# fotel_color.net
KiCad netlist of a schematic drawn in Altium Designer
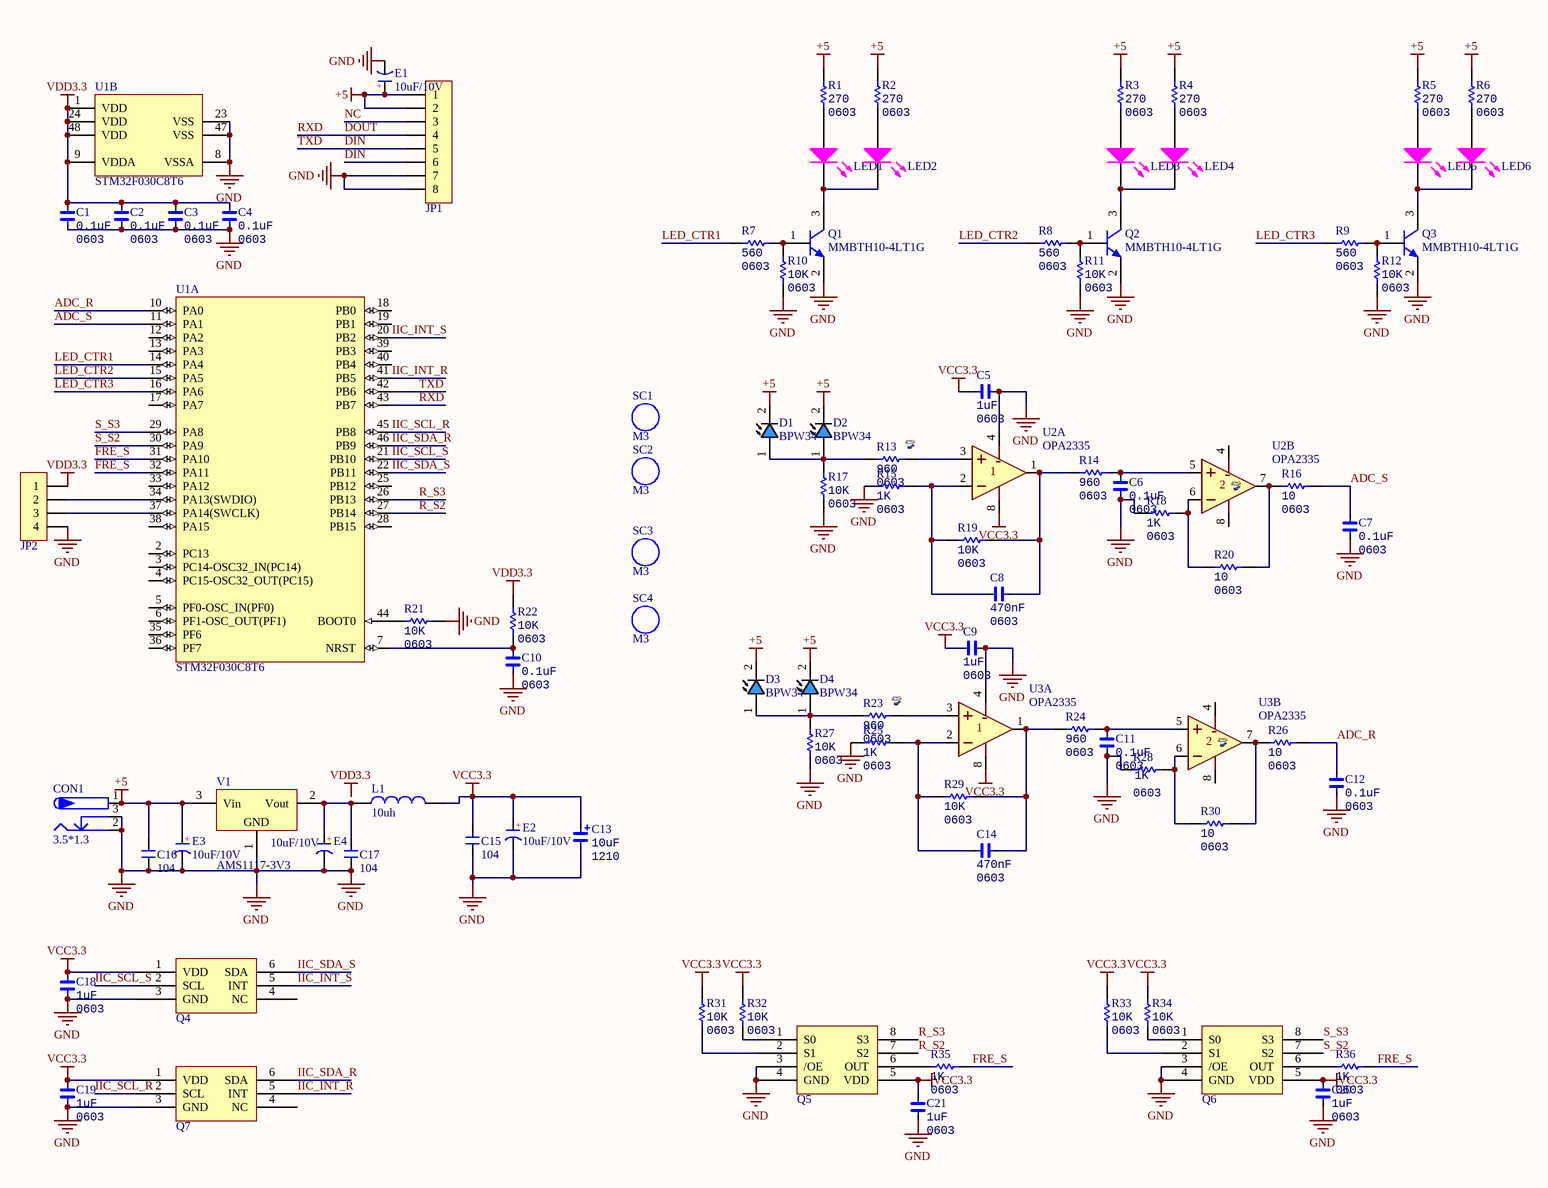
[diagram p0: fotel_color.SchDoc]

(export (version "E")
  (design (tool "Eeschema 10.0.6"))
  (components
    (comp (ref "C1")
      (value "0.1uF")
      (footprint "CAP_0603")
      (description "Capacitor")
      (fields (field (name "TYPE") "0603") (field (name "Comment") "C0402"))
      (libsource (lib "Capacitors") (part "Cap_0603"))
    )
    (comp (ref "C2")
      (value "0.1uF")
      (footprint "CAP_0603")
      (description "Capacitor")
      (fields (field (name "TYPE") "0603") (field (name "Comment") "C0402"))
      (libsource (lib "Capacitors") (part "Cap_0603"))
    )
    (comp (ref "C3")
      (value "0.1uF")
      (footprint "CAP_0603")
      (description "Capacitor")
      (fields (field (name "TYPE") "0603") (field (name "Comment") "C0402"))
      (libsource (lib "Capacitors") (part "Cap_0603"))
    )
    (comp (ref "C4")
      (value "0.1uF")
      (footprint "CAP_0603")
      (description "Capacitor")
      (fields (field (name "TYPE") "0603") (field (name "Comment") "C0402"))
      (libsource (lib "Capacitors") (part "Cap_0603"))
    )
    (comp (ref "C5")
      (value "1uF")
      (footprint "CAP_0603")
      (description "Capacitor")
      (fields (field (name "TYPE") "0603") (field (name "Comment") "C0402"))
      (libsource (lib "") (part "Cap_0603_1"))
    )
    (comp (ref "C6")
      (value "0.1uF")
      (footprint "CAP_0603")
      (description "Capacitor")
      (fields (field (name "TYPE") "0603") (field (name "Comment") "C0402"))
      (libsource (lib "Capacitors") (part "Cap_0603"))
    )
    (comp (ref "C7")
      (value "0.1uF")
      (footprint "CAP_0603")
      (description "Capacitor")
      (fields (field (name "TYPE") "0603") (field (name "Comment") "C0402"))
      (libsource (lib "Capacitors") (part "Cap_0603"))
    )
    (comp (ref "C8")
      (value "470nF")
      (footprint "CAP_0603")
      (description "Capacitor")
      (fields (field (name "TYPE") "0603") (field (name "Comment") "C0402"))
      (libsource (lib "") (part "Cap_0603_2"))
    )
    (comp (ref "C9")
      (value "1uF")
      (footprint "CAP_0603")
      (description "Capacitor")
      (fields (field (name "TYPE") "0603") (field (name "Comment") "C0402"))
      (libsource (lib "") (part "Cap_0603_1"))
    )
    (comp (ref "C10")
      (value "0.1uF")
      (footprint "CAP_0603")
      (description "Capacitor")
      (fields (field (name "TYPE") "0603") (field (name "Comment") "C0402"))
      (libsource (lib "") (part "Cap_0603_3"))
    )
    (comp (ref "C11")
      (value "0.1uF")
      (footprint "CAP_0603")
      (description "Capacitor")
      (fields (field (name "TYPE") "0603") (field (name "Comment") "C0402"))
      (libsource (lib "Capacitors") (part "Cap_0603"))
    )
    (comp (ref "C12")
      (value "0.1uF")
      (footprint "CAP_0603")
      (description "Capacitor")
      (fields (field (name "TYPE") "0603") (field (name "Comment") "C0402"))
      (libsource (lib "Capacitors") (part "Cap_0603"))
    )
    (comp (ref "C13")
      (value "10uF")
      (footprint "CAP_TAN_B1210")
      (description "Capacitor Tantalum")
      (fields (field (name "TYPE") "1210") (field (name "Comment") "C1210"))
      (libsource (lib "Capacitors") (part "Cap_Tan_1210"))
    )
    (comp (ref "C14")
      (value "470nF")
      (footprint "CAP_0603")
      (description "Capacitor")
      (fields (field (name "TYPE") "0603") (field (name "Comment") "C0402"))
      (libsource (lib "") (part "Cap_0603_2"))
    )
    (comp (ref "C15")
      (value "104")
      (footprint "C 0603")
      (description "无极性贴片电容")
      (fields (field (name "版权归属") "黎明电子style"))
      (libsource (lib "电阻-电容-电感") (part "C"))
    )
    (comp (ref "C16")
      (value "104")
      (footprint "C 0603")
      (description "无极性贴片电容")
      (fields (field (name "版权归属") "黎明电子style"))
      (libsource (lib "电阻-电容-电感") (part "C"))
    )
    (comp (ref "C17")
      (value "104")
      (footprint "C 0603")
      (description "无极性贴片电容")
      (fields (field (name "版权归属") "黎明电子style"))
      (libsource (lib "电阻-电容-电感") (part "C"))
    )
    (comp (ref "C18")
      (value "1uF")
      (footprint "CAP_0603")
      (description "Capacitor")
      (fields (field (name "TYPE") "0603") (field (name "Comment") "C0402"))
      (libsource (lib "Capacitors") (part "Cap_0603"))
    )
    (comp (ref "C19")
      (value "1uF")
      (footprint "CAP_0603")
      (description "Capacitor")
      (fields (field (name "TYPE") "0603") (field (name "Comment") "C0402"))
      (libsource (lib "Capacitors") (part "Cap_0603"))
    )
    (comp (ref "C20")
      (value "1uF")
      (footprint "CAP_0603")
      (description "Capacitor")
      (fields (field (name "TYPE") "0603") (field (name "Comment") "C0402"))
      (libsource (lib "Capacitors") (part "Cap_0603"))
    )
    (comp (ref "C21")
      (value "1uF")
      (footprint "CAP_0603")
      (description "Capacitor")
      (fields (field (name "TYPE") "0603") (field (name "Comment") "C0402"))
      (libsource (lib "Capacitors") (part "Cap_0603"))
    )
    (comp (ref "CON1")
      (value "3.5*1.3")
      (footprint "DC-005")
      (description "低压电源接口")
      (fields (field (name "版权归属") "黎明电子style"))
      (libsource (lib "接口类") (part "P-DC"))
    )
    (comp (ref "D1")
      (value "BPW34")
      (footprint "TEMD5510")
      (description "Photodiode, 2nA, 32Vr, 20ns, 60deg, 850nm")
      (fields (field (name "MANF") "OSRAM, VISHAY") (field (name "MANF_P#") "BPW34BS, BPW34S"))
      (libsource (lib "IC") (part "PHDIODE_BPW34S"))
    )
    (comp (ref "D2")
      (value "BPW34")
      (footprint "CLS15")
      (description "Photodiode, 2nA, 32Vr, 20ns, 60deg, 850nm")
      (fields (field (name "MANF") "OSRAM, VISHAY") (field (name "MANF_P#") "BPW34BS, BPW34S"))
      (libsource (lib "IC") (part "PHDIODE_BPW34S"))
    )
    (comp (ref "D3")
      (value "BPW34")
      (footprint "TEMD5510")
      (description "Photodiode, 2nA, 32Vr, 20ns, 60deg, 850nm")
      (fields (field (name "MANF") "OSRAM, VISHAY") (field (name "MANF_P#") "BPW34BS, BPW34S"))
      (libsource (lib "IC") (part "PHDIODE_BPW34S"))
    )
    (comp (ref "D4")
      (value "BPW34")
      (footprint "CLS15")
      (description "Photodiode, 2nA, 32Vr, 20ns, 60deg, 850nm")
      (fields (field (name "MANF") "OSRAM, VISHAY") (field (name "MANF_P#") "BPW34BS, BPW34S"))
      (libsource (lib "IC") (part "PHDIODE_BPW34S"))
    )
    (comp (ref "E1")
      (value "10uF/10V")
      (footprint "CM D(6.3*5.4)")
      (description "贴片电解电容")
      (fields (field (name "版权归属") "黎明电子style"))
      (libsource (lib "电阻-电容-电感") (part "C-CM"))
    )
    (comp (ref "E2")
      (value "10uF/10V")
      (footprint "CM D(6.3*5.4)")
      (description "贴片电解电容")
      (fields (field (name "版权归属") "黎明电子style"))
      (libsource (lib "电阻-电容-电感") (part "C-CM"))
    )
    (comp (ref "E3")
      (value "10uF/10V")
      (footprint "CM D(6.3*5.4)")
      (description "贴片电解电容")
      (fields (field (name "版权归属") "黎明电子style"))
      (libsource (lib "电阻-电容-电感") (part "C-CM"))
    )
    (comp (ref "E4")
      (value "10uF/10V")
      (footprint "CM D(6.3*5.4)")
      (description "贴片电解电容")
      (fields (field (name "版权归属") "黎明电子style"))
      (libsource (lib "电阻-电容-电感") (part "C-CM"))
    )
    (comp (ref "JP1")
      (value "HDR-1X8")
      (footprint "PH2.0 S-W-8P")
      (description "8P接插件")
      (fields (field (name "版权归属") "黎明电子style"))
      (libsource (lib "接插件") (part "Header 8"))
    )
    (comp (ref "JP2")
      (value "HDR-1X4")
      (footprint "XH2.54-4P")
      (description "4P接插件")
      (fields (field (name "版权归属") "黎明电子style"))
      (libsource (lib "接插件") (part "Header 4"))
    )
    (comp (ref "L1")
      (value "10uh")
      (footprint "L 0603")
      (description "小功率贴片电感")
      (fields (field (name "版权归属") "黎明电子style"))
      (libsource (lib "电阻-电容-电感") (part "L"))
    )
    (comp (ref "LED1")
      (value "LED-3-R")
      (footprint "LED-R3-H5-SINGLE-R")
      (description "Typical INFRARED GaAs LED")
      (fields (field (name "PUBLISHER") "Altium Limited"))
      (libsource (lib "(NEW)DRC_MD Library") (part "LED-3-R"))
    )
    (comp (ref "LED2")
      (value "LED-3-R")
      (footprint "LED-R3-H5-SINGLE-R")
      (description "Typical INFRARED GaAs LED")
      (fields (field (name "PUBLISHER") "Altium Limited"))
      (libsource (lib "(NEW)DRC_MD Library") (part "LED-3-R"))
    )
    (comp (ref "LED3")
      (value "LED-3-R")
      (footprint "LED-R3-H5-SINGLE-R")
      (description "Typical INFRARED GaAs LED")
      (fields (field (name "PUBLISHER") "Altium Limited"))
      (libsource (lib "(NEW)DRC_MD Library") (part "LED-3-R"))
    )
    (comp (ref "LED4")
      (value "LED-3-R")
      (footprint "LED-R3-H5-SINGLE-R")
      (description "Typical INFRARED GaAs LED")
      (fields (field (name "PUBLISHER") "Altium Limited"))
      (libsource (lib "(NEW)DRC_MD Library") (part "LED-3-R"))
    )
    (comp (ref "LED5")
      (value "LED-3-R")
      (footprint "LED-R3-H5-SINGLE-R")
      (description "Typical INFRARED GaAs LED")
      (fields (field (name "PUBLISHER") "Altium Limited"))
      (libsource (lib "(NEW)DRC_MD Library") (part "LED-3-R"))
    )
    (comp (ref "LED6")
      (value "LED-3-R")
      (footprint "LED-R3-H5-SINGLE-R")
      (description "Typical INFRARED GaAs LED")
      (fields (field (name "PUBLISHER") "Altium Limited"))
      (libsource (lib "(NEW)DRC_MD Library") (part "LED-3-R"))
    )
    (comp (ref "Q1")
      (value "MMBTH10-4LT1G")
      (footprint "ONSC-SOT-23-3-318-08_V")
      (description "VHF / UHF Transistor, NPN Silicon, 3-Pin SOT-23, Pb-Free, Tape and Reel")
      (fields (field (name "MANUFACTURER") "On Semiconductor"))
      (libsource (lib "Transistor") (part "MMBTH10-4LT1G"))
    )
    (comp (ref "Q2")
      (value "MMBTH10-4LT1G")
      (footprint "ONSC-SOT-23-3-318-08_V")
      (description "VHF / UHF Transistor, NPN Silicon, 3-Pin SOT-23, Pb-Free, Tape and Reel")
      (fields (field (name "MANUFACTURER") "On Semiconductor"))
      (libsource (lib "Transistor") (part "MMBTH10-4LT1G"))
    )
    (comp (ref "Q3")
      (value "MMBTH10-4LT1G")
      (footprint "ONSC-SOT-23-3-318-08_V")
      (description "VHF / UHF Transistor, NPN Silicon, 3-Pin SOT-23, Pb-Free, Tape and Reel")
      (fields (field (name "MANUFACTURER") "On Semiconductor"))
      (libsource (lib "Transistor") (part "MMBTH10-4LT1G"))
    )
    (comp (ref "Q4")
      (value "~")
      (footprint "TCS34725")
      (description "Phototransistor,IIC")
      (libsource (lib "IC") (part "TCS34725"))
    )
    (comp (ref "Q5")
      (value "~")
      (footprint "SOP-8")
      (description "Phototransistor,digit")
      (libsource (lib "IC") (part "TCS3200"))
    )
    (comp (ref "Q6")
      (value "~")
      (footprint "SOP-8")
      (description "Phototransistor,digit")
      (libsource (lib "IC") (part "TCS3200"))
    )
    (comp (ref "Q7")
      (value "~")
      (footprint "TCS34725")
      (description "Phototransistor,IIC")
      (libsource (lib "IC") (part "TCS34725"))
    )
    (comp (ref "R1")
      (value "270")
      (footprint "RES_0603")
      (description "Resistor")
      (fields (field (name "TYPE") "0603"))
      (libsource (lib "Resistors") (part "Res_0603"))
    )
    (comp (ref "R2")
      (value "270")
      (footprint "RES_0603")
      (description "Resistor")
      (fields (field (name "TYPE") "0603"))
      (libsource (lib "Resistors") (part "Res_0603"))
    )
    (comp (ref "R3")
      (value "270")
      (footprint "RES_0603")
      (description "Resistor")
      (fields (field (name "TYPE") "0603"))
      (libsource (lib "Resistors") (part "Res_0603"))
    )
    (comp (ref "R4")
      (value "270")
      (footprint "RES_0603")
      (description "Resistor")
      (fields (field (name "TYPE") "0603"))
      (libsource (lib "Resistors") (part "Res_0603"))
    )
    (comp (ref "R5")
      (value "270")
      (footprint "RES_0603")
      (description "Resistor")
      (fields (field (name "TYPE") "0603"))
      (libsource (lib "Resistors") (part "Res_0603"))
    )
    (comp (ref "R6")
      (value "270")
      (footprint "RES_0603")
      (description "Resistor")
      (fields (field (name "TYPE") "0603"))
      (libsource (lib "Resistors") (part "Res_0603"))
    )
    (comp (ref "R7")
      (value "560")
      (footprint "RES_0603")
      (description "Resistor")
      (fields (field (name "TYPE") "0603"))
      (libsource (lib "Resistors") (part "Res_0603"))
    )
    (comp (ref "R8")
      (value "560")
      (footprint "RES_0603")
      (description "Resistor")
      (fields (field (name "TYPE") "0603"))
      (libsource (lib "Resistors") (part "Res_0603"))
    )
    (comp (ref "R9")
      (value "560")
      (footprint "RES_0603")
      (description "Resistor")
      (fields (field (name "TYPE") "0603"))
      (libsource (lib "Resistors") (part "Res_0603"))
    )
    (comp (ref "R10")
      (value "10K")
      (footprint "RES_0603")
      (description "Resistor")
      (fields (field (name "TYPE") "0603"))
      (libsource (lib "Resistors") (part "Res_0603"))
    )
    (comp (ref "R11")
      (value "10K")
      (footprint "RES_0603")
      (description "Resistor")
      (fields (field (name "TYPE") "0603"))
      (libsource (lib "Resistors") (part "Res_0603"))
    )
    (comp (ref "R12")
      (value "10K")
      (footprint "RES_0603")
      (description "Resistor")
      (fields (field (name "TYPE") "0603"))
      (libsource (lib "Resistors") (part "Res_0603"))
    )
    (comp (ref "R13")
      (value "960")
      (footprint "RES_0603")
      (description "Resistor")
      (fields (field (name "TYPE") "0603"))
      (libsource (lib "Resistors") (part "Res_0603"))
    )
    (comp (ref "R14")
      (value "960")
      (footprint "RES_0603")
      (description "Resistor")
      (fields (field (name "TYPE") "0603"))
      (libsource (lib "Resistors") (part "Res_0603"))
    )
    (comp (ref "R15")
      (value "1K")
      (footprint "RES_0603")
      (description "Resistor")
      (fields (field (name "TYPE") "0603"))
      (libsource (lib "Resistors") (part "Res_0603"))
    )
    (comp (ref "R16")
      (value "10")
      (footprint "RES_0603")
      (description "Resistor")
      (fields (field (name "TYPE") "0603"))
      (libsource (lib "Resistors") (part "Res_0603"))
    )
    (comp (ref "R17")
      (value "10K")
      (footprint "RES_0603")
      (description "Resistor")
      (fields (field (name "TYPE") "0603"))
      (libsource (lib "Resistors") (part "Res_0603"))
    )
    (comp (ref "R18")
      (value "1K")
      (footprint "RES_0603")
      (description "Resistor")
      (fields (field (name "TYPE") "0603"))
      (libsource (lib "Resistors") (part "Res_0603"))
    )
    (comp (ref "R19")
      (value "10K")
      (footprint "RES_0603")
      (description "Resistor")
      (fields (field (name "TYPE") "0603"))
      (libsource (lib "Resistors") (part "Res_0603"))
    )
    (comp (ref "R20")
      (value "10")
      (footprint "RES_0603")
      (description "Resistor")
      (fields (field (name "TYPE") "0603"))
      (libsource (lib "Resistors") (part "Res_0603"))
    )
    (comp (ref "R21")
      (value "10K")
      (footprint "RES_0603")
      (description "Resistor")
      (fields (field (name "TYPE") "0603"))
      (libsource (lib "Resistors") (part "Res_0603"))
    )
    (comp (ref "R22")
      (value "10K")
      (footprint "RES_0603")
      (description "Resistor")
      (fields (field (name "TYPE") "0603"))
      (libsource (lib "Resistors") (part "Res_0603"))
    )
    (comp (ref "R23")
      (value "960")
      (footprint "RES_0603")
      (description "Resistor")
      (fields (field (name "TYPE") "0603"))
      (libsource (lib "Resistors") (part "Res_0603"))
    )
    (comp (ref "R24")
      (value "960")
      (footprint "RES_0603")
      (description "Resistor")
      (fields (field (name "TYPE") "0603"))
      (libsource (lib "Resistors") (part "Res_0603"))
    )
    (comp (ref "R25")
      (value "1K")
      (footprint "RES_0603")
      (description "Resistor")
      (fields (field (name "TYPE") "0603"))
      (libsource (lib "Resistors") (part "Res_0603"))
    )
    (comp (ref "R26")
      (value "10")
      (footprint "RES_0603")
      (description "Resistor")
      (fields (field (name "TYPE") "0603"))
      (libsource (lib "Resistors") (part "Res_0603"))
    )
    (comp (ref "R27")
      (value "10K")
      (footprint "RES_0603")
      (description "Resistor")
      (fields (field (name "TYPE") "0603"))
      (libsource (lib "Resistors") (part "Res_0603"))
    )
    (comp (ref "R28")
      (value "1K")
      (footprint "RES_0603")
      (description "Resistor")
      (fields (field (name "TYPE") "0603"))
      (libsource (lib "Resistors") (part "Res_0603"))
    )
    (comp (ref "R29")
      (value "10K")
      (footprint "RES_0603")
      (description "Resistor")
      (fields (field (name "TYPE") "0603"))
      (libsource (lib "Resistors") (part "Res_0603"))
    )
    (comp (ref "R30")
      (value "10")
      (footprint "RES_0603")
      (description "Resistor")
      (fields (field (name "TYPE") "0603"))
      (libsource (lib "Resistors") (part "Res_0603"))
    )
    (comp (ref "R31")
      (value "10K")
      (footprint "RES_0603")
      (description "Resistor")
      (fields (field (name "TYPE") "0603"))
      (libsource (lib "Resistors") (part "Res_0603"))
    )
    (comp (ref "R32")
      (value "10K")
      (footprint "RES_0603")
      (description "Resistor")
      (fields (field (name "TYPE") "0603"))
      (libsource (lib "Resistors") (part "Res_0603"))
    )
    (comp (ref "R33")
      (value "10K")
      (footprint "RES_0603")
      (description "Resistor")
      (fields (field (name "TYPE") "0603"))
      (libsource (lib "Resistors") (part "Res_0603"))
    )
    (comp (ref "R34")
      (value "10K")
      (footprint "RES_0603")
      (description "Resistor")
      (fields (field (name "TYPE") "0603"))
      (libsource (lib "Resistors") (part "Res_0603"))
    )
    (comp (ref "R35")
      (value "1K")
      (footprint "RES_0603")
      (description "Resistor")
      (fields (field (name "TYPE") "0603"))
      (libsource (lib "Resistors") (part "Res_0603"))
    )
    (comp (ref "R36")
      (value "1K")
      (footprint "RES_0603")
      (description "Resistor")
      (fields (field (name "TYPE") "0603"))
      (libsource (lib "Resistors") (part "Res_0603"))
    )
    (comp (ref "SC1")
      (value "M3")
      (footprint "M3 125X200")
      (description "铜柱孔")
      (fields (field (name "版权归属") "黎明电子style"))
      (libsource (lib "未分类器件") (part "M3"))
    )
    (comp (ref "SC2")
      (value "M3")
      (footprint "M3 125X200")
      (description "铜柱孔")
      (fields (field (name "版权归属") "黎明电子style"))
      (libsource (lib "未分类器件") (part "M3"))
    )
    (comp (ref "SC3")
      (value "M3")
      (footprint "M3 125X200")
      (description "铜柱孔")
      (fields (field (name "版权归属") "黎明电子style"))
      (libsource (lib "未分类器件") (part "M3"))
    )
    (comp (ref "SC4")
      (value "M3")
      (footprint "M3 125X200")
      (description "铜柱孔")
      (fields (field (name "版权归属") "黎明电子style"))
      (libsource (lib "未分类器件") (part "M3"))
    )
    (comp (ref "U1")
      (value "STM32F030C8T6")
      (footprint "LQFP48 7X7_M")
      (libsource (lib "IC") (part "STM32F030C8T6"))
    )
    (comp (ref "U2")
      (value "OPA2335")
      (footprint "SOG65_8_3")
      (description "AMP, Low Offset, Zero Drift, Single-Supply")
      (fields (field (name "MANF") "Texas Instruments") (field (name "MANF_P#") "OPA2335AIDGK"))
      (libsource (lib "IC") (part "OPA2335_SSOP8"))
    )
    (comp (ref "U3")
      (value "OPA2335")
      (footprint "SOG65_8_3")
      (description "AMP, Low Offset, Zero Drift, Single-Supply")
      (fields (field (name "MANF") "Texas Instruments") (field (name "MANF_P#") "OPA2335AIDGK"))
      (libsource (lib "IC") (part "OPA2335_SSOP8"))
    )
    (comp (ref "V1")
      (value "AMS1117-3V3")
      (footprint "SOT223_L")
      (description "三端稳压芯片")
      (fields (field (name "版权归属") "黎明电子style"))
      (libsource (lib "IC芯片") (part "AMS1117"))
    )
  )
  (nets
    (net (code "1") (name "+5") (class "Default")
      (node (ref "C16") (pin "2") (pinfunction "2_2") (pintype "passive"))
      (node (ref "CON1") (pin "1") (pintype "power_in"))
      (node (ref "D1") (pin "2") (pinfunction "CATHODE_2") (pintype "passive"))
      (node (ref "D2") (pin "2") (pinfunction "CATHODE_2") (pintype "passive"))
      (node (ref "D3") (pin "2") (pinfunction "CATHODE_2") (pintype "passive"))
      (node (ref "D4") (pin "2") (pinfunction "CATHODE_2") (pintype "passive"))
      (node (ref "E1") (pin "1") (pinfunction "A_1") (pintype "passive"))
      (node (ref "E3") (pin "1") (pinfunction "A_1") (pintype "passive"))
      (node (ref "JP1") (pin "1") (pinfunction "1_1") (pintype "passive"))
      (node (ref "JP1") (pin "2") (pinfunction "2_2") (pintype "passive"))
      (node (ref "R1") (pin "2") (pinfunction "2_2") (pintype "passive"))
      (node (ref "R2") (pin "2") (pinfunction "2_2") (pintype "passive"))
      (node (ref "R3") (pin "2") (pinfunction "2_2") (pintype "passive"))
      (node (ref "R4") (pin "2") (pinfunction "2_2") (pintype "passive"))
      (node (ref "R5") (pin "2") (pinfunction "2_2") (pintype "passive"))
      (node (ref "R6") (pin "2") (pinfunction "2_2") (pintype "passive"))
      (node (ref "V1") (pin "3") (pinfunction "Vin_3") (pintype "passive"))
    )
    (net (code "2") (name "/ADC_R") (class "Default")
      (node (ref "C12") (pin "1") (pinfunction "1_1") (pintype "passive"))
      (node (ref "R26") (pin "2") (pinfunction "2_2") (pintype "passive"))
      (node (ref "U1") (pin "10") (pinfunction "PA0_10") (pintype "bidirectional"))
    )
    (net (code "3") (name "/ADC_S") (class "Default")
      (node (ref "C7") (pin "1") (pinfunction "1_1") (pintype "passive"))
      (node (ref "R16") (pin "2") (pinfunction "2_2") (pintype "passive"))
      (node (ref "U1") (pin "11") (pinfunction "PA1_11") (pintype "bidirectional"))
    )
    (net (code "4") (name "/DIN") (class "Default")
      (node (ref "JP1") (pin "5") (pinfunction "5_5") (pintype "passive"))
      (node (ref "JP1") (pin "6") (pinfunction "6_6") (pintype "passive"))
      (node (ref "U1") (pin "42") (pinfunction "PB6_42") (pintype "bidirectional"))
    )
    (net (code "5") (name "/DOUT") (class "Default")
      (node (ref "JP1") (pin "4") (pinfunction "4_4") (pintype "passive"))
      (node (ref "U1") (pin "43") (pinfunction "PB7_43") (pintype "bidirectional"))
    )
    (net (code "6") (name "/FRE_S") (class "Default")
      (node (ref "R35") (pin "1") (pinfunction "1_1") (pintype "passive"))
      (node (ref "R36") (pin "1") (pinfunction "1_1") (pintype "passive"))
      (node (ref "U1") (pin "31") (pinfunction "PA10_31") (pintype "bidirectional"))
      (node (ref "U1") (pin "32") (pinfunction "PA11_32") (pintype "bidirectional"))
    )
    (net (code "7") (name "/IIC_INT_R") (class "Default")
      (node (ref "Q7") (pin "5") (pinfunction "INT_5") (pintype "passive"))
      (node (ref "U1") (pin "41") (pinfunction "PB5_41") (pintype "bidirectional"))
    )
    (net (code "8") (name "/IIC_INT_S") (class "Default")
      (node (ref "Q4") (pin "5") (pinfunction "INT_5") (pintype "passive"))
      (node (ref "U1") (pin "20") (pinfunction "PB2_20") (pintype "bidirectional"))
    )
    (net (code "9") (name "/IIC_SCL_R") (class "Default")
      (node (ref "Q7") (pin "2") (pinfunction "SCL_2") (pintype "passive"))
      (node (ref "U1") (pin "45") (pinfunction "PB8_45") (pintype "bidirectional"))
    )
    (net (code "10") (name "/IIC_SCL_S") (class "Default")
      (node (ref "Q4") (pin "2") (pinfunction "SCL_2") (pintype "passive"))
      (node (ref "U1") (pin "21") (pinfunction "PB10_21") (pintype "bidirectional"))
    )
    (net (code "11") (name "/IIC_SDA_R") (class "Default")
      (node (ref "Q7") (pin "6") (pinfunction "SDA_6") (pintype "passive"))
      (node (ref "U1") (pin "46") (pinfunction "PB9_46") (pintype "bidirectional"))
    )
    (net (code "12") (name "/IIC_SDA_S") (class "Default")
      (node (ref "Q4") (pin "6") (pinfunction "SDA_6") (pintype "passive"))
      (node (ref "U1") (pin "22") (pinfunction "PB11_22") (pintype "bidirectional"))
    )
    (net (code "13") (name "/LED_CTR1") (class "Default")
      (node (ref "R7") (pin "1") (pinfunction "1_1") (pintype "passive"))
      (node (ref "U1") (pin "14") (pinfunction "PA4_14") (pintype "bidirectional"))
    )
    (net (code "14") (name "/LED_CTR2") (class "Default")
      (node (ref "R8") (pin "1") (pinfunction "1_1") (pintype "passive"))
      (node (ref "U1") (pin "15") (pinfunction "PA5_15") (pintype "bidirectional"))
    )
    (net (code "15") (name "/LED_CTR3") (class "Default")
      (node (ref "R9") (pin "1") (pinfunction "1_1") (pintype "passive"))
      (node (ref "U1") (pin "16") (pinfunction "PA6_16") (pintype "bidirectional"))
    )
    (net (code "16") (name "/NC") (class "Default")
      (node (ref "JP1") (pin "3") (pinfunction "3_3") (pintype "passive"))
    )
    (net (code "17") (name "/R_S2") (class "Default")
      (node (ref "Q5") (pin "7") (pinfunction "S2_7") (pintype "passive"))
      (node (ref "U1") (pin "27") (pinfunction "PB14_27") (pintype "bidirectional"))
    )
    (net (code "18") (name "/R_S3") (class "Default")
      (node (ref "Q5") (pin "8") (pinfunction "S3_8") (pintype "passive"))
      (node (ref "U1") (pin "26") (pinfunction "PB13_26") (pintype "bidirectional"))
    )
    (net (code "19") (name "/S_S2") (class "Default")
      (node (ref "Q6") (pin "7") (pinfunction "S2_7") (pintype "passive"))
      (node (ref "U1") (pin "30") (pinfunction "PA9_30") (pintype "bidirectional"))
    )
    (net (code "20") (name "/S_S3") (class "Default")
      (node (ref "Q6") (pin "8") (pinfunction "S3_8") (pintype "passive"))
      (node (ref "U1") (pin "29") (pinfunction "PA8_29") (pintype "bidirectional"))
    )
    (net (code "21") (name "GND") (class "Default")
      (node (ref "C1") (pin "2") (pinfunction "2_2") (pintype "passive"))
      (node (ref "C10") (pin "1") (pinfunction "1_1") (pintype "passive"))
      (node (ref "C11") (pin "2") (pinfunction "2_2") (pintype "passive"))
      (node (ref "C12") (pin "2") (pinfunction "2_2") (pintype "passive"))
      (node (ref "C13") (pin "2") (pinfunction "2_2") (pintype "passive"))
      (node (ref "C15") (pin "1") (pinfunction "1_1") (pintype "passive"))
      (node (ref "C16") (pin "1") (pinfunction "1_1") (pintype "passive"))
      (node (ref "C17") (pin "1") (pinfunction "1_1") (pintype "passive"))
      (node (ref "C18") (pin "2") (pinfunction "2_2") (pintype "passive"))
      (node (ref "C19") (pin "2") (pinfunction "2_2") (pintype "passive"))
      (node (ref "C2") (pin "2") (pinfunction "2_2") (pintype "passive"))
      (node (ref "C20") (pin "2") (pinfunction "2_2") (pintype "passive"))
      (node (ref "C21") (pin "2") (pinfunction "2_2") (pintype "passive"))
      (node (ref "C3") (pin "2") (pinfunction "2_2") (pintype "passive"))
      (node (ref "C4") (pin "2") (pinfunction "2_2") (pintype "passive"))
      (node (ref "C5") (pin "2") (pinfunction "2_2") (pintype "passive"))
      (node (ref "C6") (pin "2") (pinfunction "2_2") (pintype "passive"))
      (node (ref "C7") (pin "2") (pinfunction "2_2") (pintype "passive"))
      (node (ref "C9") (pin "2") (pinfunction "2_2") (pintype "passive"))
      (node (ref "CON1") (pin "2") (pintype "power_in"))
      (node (ref "CON1") (pin "3") (pintype "power_in"))
      (node (ref "E1") (pin "2") (pinfunction "K_2") (pintype "passive"))
      (node (ref "E2") (pin "2") (pinfunction "K_2") (pintype "passive"))
      (node (ref "E3") (pin "2") (pinfunction "K_2") (pintype "passive"))
      (node (ref "E4") (pin "2") (pinfunction "K_2") (pintype "passive"))
      (node (ref "JP1") (pin "7") (pinfunction "7_7") (pintype "passive"))
      (node (ref "JP1") (pin "8") (pinfunction "8_8") (pintype "passive"))
      (node (ref "JP2") (pin "4") (pinfunction "4_4") (pintype "passive"))
      (node (ref "Q1") (pin "2") (pinfunction "E_2") (pintype "passive"))
      (node (ref "Q2") (pin "2") (pinfunction "E_2") (pintype "passive"))
      (node (ref "Q3") (pin "2") (pinfunction "E_2") (pintype "passive"))
      (node (ref "Q4") (pin "3") (pinfunction "GND_3") (pintype "passive"))
      (node (ref "Q5") (pin "3") (pinfunction "/OE_3") (pintype "passive"))
      (node (ref "Q5") (pin "4") (pinfunction "GND_4") (pintype "passive"))
      (node (ref "Q6") (pin "3") (pinfunction "/OE_3") (pintype "passive"))
      (node (ref "Q6") (pin "4") (pinfunction "GND_4") (pintype "passive"))
      (node (ref "Q7") (pin "3") (pinfunction "GND_3") (pintype "passive"))
      (node (ref "R10") (pin "1") (pinfunction "1_1") (pintype "passive"))
      (node (ref "R11") (pin "1") (pinfunction "1_1") (pintype "passive"))
      (node (ref "R12") (pin "1") (pinfunction "1_1") (pintype "passive"))
      (node (ref "R15") (pin "1") (pinfunction "1_1") (pintype "passive"))
      (node (ref "R17") (pin "1") (pinfunction "1_1") (pintype "passive"))
      (node (ref "R18") (pin "1") (pinfunction "1_1") (pintype "passive"))
      (node (ref "R21") (pin "2") (pinfunction "2_2") (pintype "passive"))
      (node (ref "R25") (pin "1") (pinfunction "1_1") (pintype "passive"))
      (node (ref "R27") (pin "1") (pinfunction "1_1") (pintype "passive"))
      (node (ref "R28") (pin "1") (pinfunction "1_1") (pintype "passive"))
      (node (ref "U1") (pin "23") (pinfunction "VSS_23") (pintype "power_in"))
      (node (ref "U1") (pin "47") (pinfunction "VSS_47") (pintype "power_in"))
      (node (ref "U1") (pin "8") (pinfunction "VSSA_8") (pintype "power_in"))
      (node (ref "U2") (pin "4") (pinfunction "V-_4") (pintype "passive"))
      (node (ref "U3") (pin "4") (pinfunction "V-_4") (pintype "passive"))
      (node (ref "V1") (pin "1") (pinfunction "GND_1") (pintype "passive"))
    )
    (net (code "22") (name "Net-(D1-ANODE)") (class "Default")
      (node (ref "D1") (pin "1") (pinfunction "ANODE_1") (pintype "passive"))
      (node (ref "D2") (pin "1") (pinfunction "ANODE_1") (pintype "passive"))
      (node (ref "R13") (pin "1") (pinfunction "1_1") (pintype "passive"))
      (node (ref "R17") (pin "2") (pinfunction "2_2") (pintype "passive"))
    )
    (net (code "23") (name "Net-(D3-ANODE)") (class "Default")
      (node (ref "D3") (pin "1") (pinfunction "ANODE_1") (pintype "passive"))
      (node (ref "D4") (pin "1") (pinfunction "ANODE_1") (pintype "passive"))
      (node (ref "R23") (pin "1") (pinfunction "1_1") (pintype "passive"))
      (node (ref "R27") (pin "2") (pinfunction "2_2") (pintype "passive"))
    )
    (net (code "24") (name "Net-(E4-A)") (class "Default")
      (node (ref "C17") (pin "2") (pinfunction "2_2") (pintype "passive"))
      (node (ref "E4") (pin "1") (pinfunction "A_1") (pintype "passive"))
      (node (ref "L1") (pin "1") (pinfunction "1_1") (pintype "passive"))
      (node (ref "V1") (pin "2") (pinfunction "Vout_2") (pintype "passive"))
    )
    (net (code "25") (name "Net-(LED1-A)") (class "Default")
      (node (ref "LED1") (pin "1") (pinfunction "A_1") (pintype "passive"))
      (node (ref "R1") (pin "1") (pinfunction "1_1") (pintype "passive"))
    )
    (net (code "26") (name "Net-(LED1-K)") (class "Default")
      (node (ref "LED1") (pin "2") (pinfunction "K_2") (pintype "passive"))
      (node (ref "LED2") (pin "2") (pinfunction "K_2") (pintype "passive"))
      (node (ref "Q1") (pin "3") (pinfunction "C_3") (pintype "passive"))
    )
    (net (code "27") (name "Net-(LED2-A)") (class "Default")
      (node (ref "LED2") (pin "1") (pinfunction "A_1") (pintype "passive"))
      (node (ref "R2") (pin "1") (pinfunction "1_1") (pintype "passive"))
    )
    (net (code "28") (name "Net-(LED3-A)") (class "Default")
      (node (ref "LED3") (pin "1") (pinfunction "A_1") (pintype "passive"))
      (node (ref "R3") (pin "1") (pinfunction "1_1") (pintype "passive"))
    )
    (net (code "29") (name "Net-(LED3-K)") (class "Default")
      (node (ref "LED3") (pin "2") (pinfunction "K_2") (pintype "passive"))
      (node (ref "LED4") (pin "2") (pinfunction "K_2") (pintype "passive"))
      (node (ref "Q2") (pin "3") (pinfunction "C_3") (pintype "passive"))
    )
    (net (code "30") (name "Net-(LED4-A)") (class "Default")
      (node (ref "LED4") (pin "1") (pinfunction "A_1") (pintype "passive"))
      (node (ref "R4") (pin "1") (pinfunction "1_1") (pintype "passive"))
    )
    (net (code "31") (name "Net-(LED5-A)") (class "Default")
      (node (ref "LED5") (pin "1") (pinfunction "A_1") (pintype "passive"))
      (node (ref "R5") (pin "1") (pinfunction "1_1") (pintype "passive"))
    )
    (net (code "32") (name "Net-(LED5-K)") (class "Default")
      (node (ref "LED5") (pin "2") (pinfunction "K_2") (pintype "passive"))
      (node (ref "LED6") (pin "2") (pinfunction "K_2") (pintype "passive"))
      (node (ref "Q3") (pin "3") (pinfunction "C_3") (pintype "passive"))
    )
    (net (code "33") (name "Net-(LED6-A)") (class "Default")
      (node (ref "LED6") (pin "1") (pinfunction "A_1") (pintype "passive"))
      (node (ref "R6") (pin "1") (pinfunction "1_1") (pintype "passive"))
    )
    (net (code "34") (name "Net-(Q1-B)") (class "Default")
      (node (ref "Q1") (pin "1") (pinfunction "B_1") (pintype "passive"))
      (node (ref "R10") (pin "2") (pinfunction "2_2") (pintype "passive"))
      (node (ref "R7") (pin "2") (pinfunction "2_2") (pintype "passive"))
    )
    (net (code "35") (name "Net-(Q2-B)") (class "Default")
      (node (ref "Q2") (pin "1") (pinfunction "B_1") (pintype "passive"))
      (node (ref "R11") (pin "2") (pinfunction "2_2") (pintype "passive"))
      (node (ref "R8") (pin "2") (pinfunction "2_2") (pintype "passive"))
    )
    (net (code "36") (name "Net-(Q3-B)") (class "Default")
      (node (ref "Q3") (pin "1") (pinfunction "B_1") (pintype "passive"))
      (node (ref "R12") (pin "2") (pinfunction "2_2") (pintype "passive"))
      (node (ref "R9") (pin "2") (pinfunction "2_2") (pintype "passive"))
    )
    (net (code "37") (name "Net-(Q5-OUT)") (class "Default")
      (node (ref "Q5") (pin "6") (pinfunction "OUT_6") (pintype "passive"))
      (node (ref "R35") (pin "2") (pinfunction "2_2") (pintype "passive"))
    )
    (net (code "38") (name "Net-(Q5-S0)") (class "Default")
      (node (ref "Q5") (pin "1") (pinfunction "S0_1") (pintype "passive"))
      (node (ref "R32") (pin "1") (pinfunction "1_1") (pintype "passive"))
    )
    (net (code "39") (name "Net-(Q5-S1)") (class "Default")
      (node (ref "Q5") (pin "2") (pinfunction "S1_2") (pintype "passive"))
      (node (ref "R31") (pin "1") (pinfunction "1_1") (pintype "passive"))
    )
    (net (code "40") (name "Net-(Q6-OUT)") (class "Default")
      (node (ref "Q6") (pin "6") (pinfunction "OUT_6") (pintype "passive"))
      (node (ref "R36") (pin "2") (pinfunction "2_2") (pintype "passive"))
    )
    (net (code "41") (name "Net-(Q6-S0)") (class "Default")
      (node (ref "Q6") (pin "1") (pinfunction "S0_1") (pintype "passive"))
      (node (ref "R34") (pin "1") (pinfunction "1_1") (pintype "passive"))
    )
    (net (code "42") (name "Net-(Q6-S1)") (class "Default")
      (node (ref "Q6") (pin "2") (pinfunction "S1_2") (pintype "passive"))
      (node (ref "R33") (pin "1") (pinfunction "1_1") (pintype "passive"))
    )
    (net (code "43") (name "Net-(U1A-BOOT0)") (class "Default")
      (node (ref "R21") (pin "1") (pinfunction "1_1") (pintype "passive"))
      (node (ref "U1") (pin "44") (pinfunction "BOOT0_44") (pintype "input"))
    )
    (net (code "44") (name "Net-(U1A-NRST)") (class "Default")
      (node (ref "C10") (pin "2") (pinfunction "2_2") (pintype "passive"))
      (node (ref "R22") (pin "2") (pinfunction "2_2") (pintype "passive"))
      (node (ref "U1") (pin "7") (pinfunction "NRST_7") (pintype "bidirectional"))
    )
    (net (code "45") (name "Net-(U1A-PA13(SWDIO))") (class "Default")
      (node (ref "JP2") (pin "2") (pinfunction "2_2") (pintype "passive"))
      (node (ref "U1") (pin "34") (pinfunction "PA13(SWDIO)_34") (pintype "bidirectional"))
    )
    (net (code "46") (name "Net-(U1A-PA14(SWCLK))") (class "Default")
      (node (ref "JP2") (pin "3") (pinfunction "3_3") (pintype "passive"))
      (node (ref "U1") (pin "37") (pinfunction "PA14(SWCLK)_37") (pintype "bidirectional"))
    )
    (net (code "47") (name "Net-(U2A-IN+)") (class "Default")
      (node (ref "R13") (pin "2") (pinfunction "2_2") (pintype "passive"))
      (node (ref "U2") (pin "3") (pinfunction "IN+_3") (pintype "passive"))
    )
    (net (code "48") (name "Net-(U2A-IN-)") (class "Default")
      (node (ref "C8") (pin "2") (pinfunction "2_2") (pintype "passive"))
      (node (ref "R15") (pin "2") (pinfunction "2_2") (pintype "passive"))
      (node (ref "R19") (pin "1") (pinfunction "1_1") (pintype "passive"))
      (node (ref "U2") (pin "2") (pinfunction "IN-_2") (pintype "passive"))
    )
    (net (code "49") (name "Net-(U2A-OUT)") (class "Default")
      (node (ref "C8") (pin "1") (pinfunction "1_1") (pintype "passive"))
      (node (ref "R14") (pin "1") (pinfunction "1_1") (pintype "passive"))
      (node (ref "R19") (pin "2") (pinfunction "2_2") (pintype "passive"))
      (node (ref "U2") (pin "1") (pinfunction "OUT_1") (pintype "passive"))
    )
    (net (code "50") (name "Net-(U2B-IN+)") (class "Default")
      (node (ref "C6") (pin "1") (pinfunction "1_1") (pintype "passive"))
      (node (ref "R14") (pin "2") (pinfunction "2_2") (pintype "passive"))
      (node (ref "U2") (pin "5") (pinfunction "IN+_5") (pintype "passive"))
    )
    (net (code "51") (name "Net-(U2B-IN-)") (class "Default")
      (node (ref "R18") (pin "2") (pinfunction "2_2") (pintype "passive"))
      (node (ref "R20") (pin "1") (pinfunction "1_1") (pintype "passive"))
      (node (ref "U2") (pin "6") (pinfunction "IN-_6") (pintype "passive"))
    )
    (net (code "52") (name "Net-(U2B-OUT)") (class "Default")
      (node (ref "R16") (pin "1") (pinfunction "1_1") (pintype "passive"))
      (node (ref "R20") (pin "2") (pinfunction "2_2") (pintype "passive"))
      (node (ref "U2") (pin "7") (pinfunction "OUT_7") (pintype "passive"))
    )
    (net (code "53") (name "Net-(U3A-IN+)") (class "Default")
      (node (ref "R23") (pin "2") (pinfunction "2_2") (pintype "passive"))
      (node (ref "U3") (pin "3") (pinfunction "IN+_3") (pintype "passive"))
    )
    (net (code "54") (name "Net-(U3A-IN-)") (class "Default")
      (node (ref "C14") (pin "2") (pinfunction "2_2") (pintype "passive"))
      (node (ref "R25") (pin "2") (pinfunction "2_2") (pintype "passive"))
      (node (ref "R29") (pin "1") (pinfunction "1_1") (pintype "passive"))
      (node (ref "U3") (pin "2") (pinfunction "IN-_2") (pintype "passive"))
    )
    (net (code "55") (name "Net-(U3A-OUT)") (class "Default")
      (node (ref "C14") (pin "1") (pinfunction "1_1") (pintype "passive"))
      (node (ref "R24") (pin "1") (pinfunction "1_1") (pintype "passive"))
      (node (ref "R29") (pin "2") (pinfunction "2_2") (pintype "passive"))
      (node (ref "U3") (pin "1") (pinfunction "OUT_1") (pintype "passive"))
    )
    (net (code "56") (name "Net-(U3B-IN+)") (class "Default")
      (node (ref "C11") (pin "1") (pinfunction "1_1") (pintype "passive"))
      (node (ref "R24") (pin "2") (pinfunction "2_2") (pintype "passive"))
      (node (ref "U3") (pin "5") (pinfunction "IN+_5") (pintype "passive"))
    )
    (net (code "57") (name "Net-(U3B-IN-)") (class "Default")
      (node (ref "R28") (pin "2") (pinfunction "2_2") (pintype "passive"))
      (node (ref "R30") (pin "1") (pinfunction "1_1") (pintype "passive"))
      (node (ref "U3") (pin "6") (pinfunction "IN-_6") (pintype "passive"))
    )
    (net (code "58") (name "Net-(U3B-OUT)") (class "Default")
      (node (ref "R26") (pin "1") (pinfunction "1_1") (pintype "passive"))
      (node (ref "R30") (pin "2") (pinfunction "2_2") (pintype "passive"))
      (node (ref "U3") (pin "7") (pinfunction "OUT_7") (pintype "passive"))
    )
    (net (code "59") (name "VCC3.3") (class "Default")
      (node (ref "C13") (pin "1") (pinfunction "1_1") (pintype "passive"))
      (node (ref "C15") (pin "2") (pinfunction "2_2") (pintype "passive"))
      (node (ref "C18") (pin "1") (pinfunction "1_1") (pintype "passive"))
      (node (ref "C19") (pin "1") (pinfunction "1_1") (pintype "passive"))
      (node (ref "C20") (pin "1") (pinfunction "1_1") (pintype "passive"))
      (node (ref "C21") (pin "1") (pinfunction "1_1") (pintype "passive"))
      (node (ref "C5") (pin "1") (pinfunction "1_1") (pintype "passive"))
      (node (ref "C9") (pin "1") (pinfunction "1_1") (pintype "passive"))
      (node (ref "E2") (pin "1") (pinfunction "A_1") (pintype "passive"))
      (node (ref "L1") (pin "2") (pinfunction "2_2") (pintype "passive"))
      (node (ref "Q4") (pin "1") (pinfunction "VDD_1") (pintype "passive"))
      (node (ref "Q5") (pin "5") (pinfunction "VDD_5") (pintype "passive"))
      (node (ref "Q6") (pin "5") (pinfunction "VDD_5") (pintype "passive"))
      (node (ref "Q7") (pin "1") (pinfunction "VDD_1") (pintype "passive"))
      (node (ref "R31") (pin "2") (pinfunction "2_2") (pintype "passive"))
      (node (ref "R32") (pin "2") (pinfunction "2_2") (pintype "passive"))
      (node (ref "R33") (pin "2") (pinfunction "2_2") (pintype "passive"))
      (node (ref "R34") (pin "2") (pinfunction "2_2") (pintype "passive"))
      (node (ref "U2") (pin "8") (pinfunction "V+_8") (pintype "passive"))
      (node (ref "U3") (pin "8") (pinfunction "V+_8") (pintype "passive"))
    )
    (net (code "60") (name "VDD3.3") (class "Default")
      (node (ref "C1") (pin "1") (pinfunction "1_1") (pintype "passive"))
      (node (ref "C2") (pin "1") (pinfunction "1_1") (pintype "passive"))
      (node (ref "C3") (pin "1") (pinfunction "1_1") (pintype "passive"))
      (node (ref "C4") (pin "1") (pinfunction "1_1") (pintype "passive"))
      (node (ref "JP2") (pin "1") (pinfunction "1_1") (pintype "passive"))
      (node (ref "R22") (pin "1") (pinfunction "1_1") (pintype "passive"))
      (node (ref "U1") (pin "1") (pinfunction "VDD_1") (pintype "power_in"))
      (node (ref "U1") (pin "24") (pinfunction "VDD_24") (pintype "power_in"))
      (node (ref "U1") (pin "48") (pinfunction "VDD_48") (pintype "power_in"))
      (node (ref "U1") (pin "9") (pinfunction "VDDA_9") (pintype "power_in"))
    )
    (net (code "61") (name "unconnected-(Q4-NC-Pad4)") (class "Default")
      (node (ref "Q4") (pin "4") (pinfunction "NC_4") (pintype "passive"))
    )
    (net (code "62") (name "unconnected-(Q7-NC-Pad4)") (class "Default")
      (node (ref "Q7") (pin "4") (pinfunction "NC_4") (pintype "passive"))
    )
    (net (code "63") (name "unconnected-(U1A-PA2-Pad12)") (class "Default")
      (node (ref "U1") (pin "12") (pinfunction "PA2_12") (pintype "bidirectional"))
    )
    (net (code "64") (name "unconnected-(U1A-PA3-Pad13)") (class "Default")
      (node (ref "U1") (pin "13") (pinfunction "PA3_13") (pintype "bidirectional"))
    )
    (net (code "65") (name "unconnected-(U1A-PA7-Pad17)") (class "Default")
      (node (ref "U1") (pin "17") (pinfunction "PA7_17") (pintype "bidirectional"))
    )
    (net (code "66") (name "unconnected-(U1A-PA12-Pad33)") (class "Default")
      (node (ref "U1") (pin "33") (pinfunction "PA12_33") (pintype "bidirectional"))
    )
    (net (code "67") (name "unconnected-(U1A-PA15-Pad38)") (class "Default")
      (node (ref "U1") (pin "38") (pinfunction "PA15_38") (pintype "bidirectional"))
    )
    (net (code "68") (name "unconnected-(U1A-PB0-Pad18)") (class "Default")
      (node (ref "U1") (pin "18") (pinfunction "PB0_18") (pintype "bidirectional"))
    )
    (net (code "69") (name "unconnected-(U1A-PB1-Pad19)") (class "Default")
      (node (ref "U1") (pin "19") (pinfunction "PB1_19") (pintype "bidirectional"))
    )
    (net (code "70") (name "unconnected-(U1A-PB3-Pad39)") (class "Default")
      (node (ref "U1") (pin "39") (pinfunction "PB3_39") (pintype "bidirectional"))
    )
    (net (code "71") (name "unconnected-(U1A-PB4-Pad40)") (class "Default")
      (node (ref "U1") (pin "40") (pinfunction "PB4_40") (pintype "bidirectional"))
    )
    (net (code "72") (name "unconnected-(U1A-PB12-Pad25)") (class "Default")
      (node (ref "U1") (pin "25") (pinfunction "PB12_25") (pintype "bidirectional"))
    )
    (net (code "73") (name "unconnected-(U1A-PB15-Pad28)") (class "Default")
      (node (ref "U1") (pin "28") (pinfunction "PB15_28") (pintype "bidirectional"))
    )
    (net (code "74") (name "unconnected-(U1A-PC13-Pad2)") (class "Default")
      (node (ref "U1") (pin "2") (pinfunction "PC13_2") (pintype "bidirectional"))
    )
    (net (code "75") (name "unconnected-(U1A-PC14-OSC32_IN(PC14)-Pad3)") (class "Default")
      (node (ref "U1") (pin "3") (pinfunction "PC14-OSC32_IN(PC14)_3") (pintype "bidirectional"))
    )
    (net (code "76") (name "unconnected-(U1A-PC15-OSC32_OUT(PC15)-Pad4)") (class "Default")
      (node (ref "U1") (pin "4") (pinfunction "PC15-OSC32_OUT(PC15)_4") (pintype "bidirectional"))
    )
    (net (code "77") (name "unconnected-(U1A-PF0-OSC_IN(PF0)-Pad5)") (class "Default")
      (node (ref "U1") (pin "5") (pinfunction "PF0-OSC_IN(PF0)_5") (pintype "bidirectional"))
    )
    (net (code "78") (name "unconnected-(U1A-PF1-OSC_OUT(PF1)-Pad6)") (class "Default")
      (node (ref "U1") (pin "6") (pinfunction "PF1-OSC_OUT(PF1)_6") (pintype "bidirectional"))
    )
    (net (code "79") (name "unconnected-(U1A-PF6-Pad35)") (class "Default")
      (node (ref "U1") (pin "35") (pinfunction "PF6_35") (pintype "bidirectional"))
    )
    (net (code "80") (name "unconnected-(U1A-PF7-Pad36)") (class "Default")
      (node (ref "U1") (pin "36") (pinfunction "PF7_36") (pintype "bidirectional"))
    )
    (net (code "81") (name "unconnected-(U2B-V+-Pad8)") (class "Default")
      (node (ref "U2") (pin "8") (pinfunction "V+_8") (pintype "passive"))
    )
    (net (code "82") (name "unconnected-(U2B-V--Pad4)") (class "Default")
      (node (ref "U2") (pin "4") (pinfunction "V-_4") (pintype "passive"))
    )
    (net (code "83") (name "unconnected-(U3B-V+-Pad8)") (class "Default")
      (node (ref "U3") (pin "8") (pinfunction "V+_8") (pintype "passive"))
    )
    (net (code "84") (name "unconnected-(U3B-V--Pad4)") (class "Default")
      (node (ref "U3") (pin "4") (pinfunction "V-_4") (pintype "passive"))
    )
  )
)
